# SKYSTAR.net
KiCad netlist of a schematic drawn in EasyEDA Pro
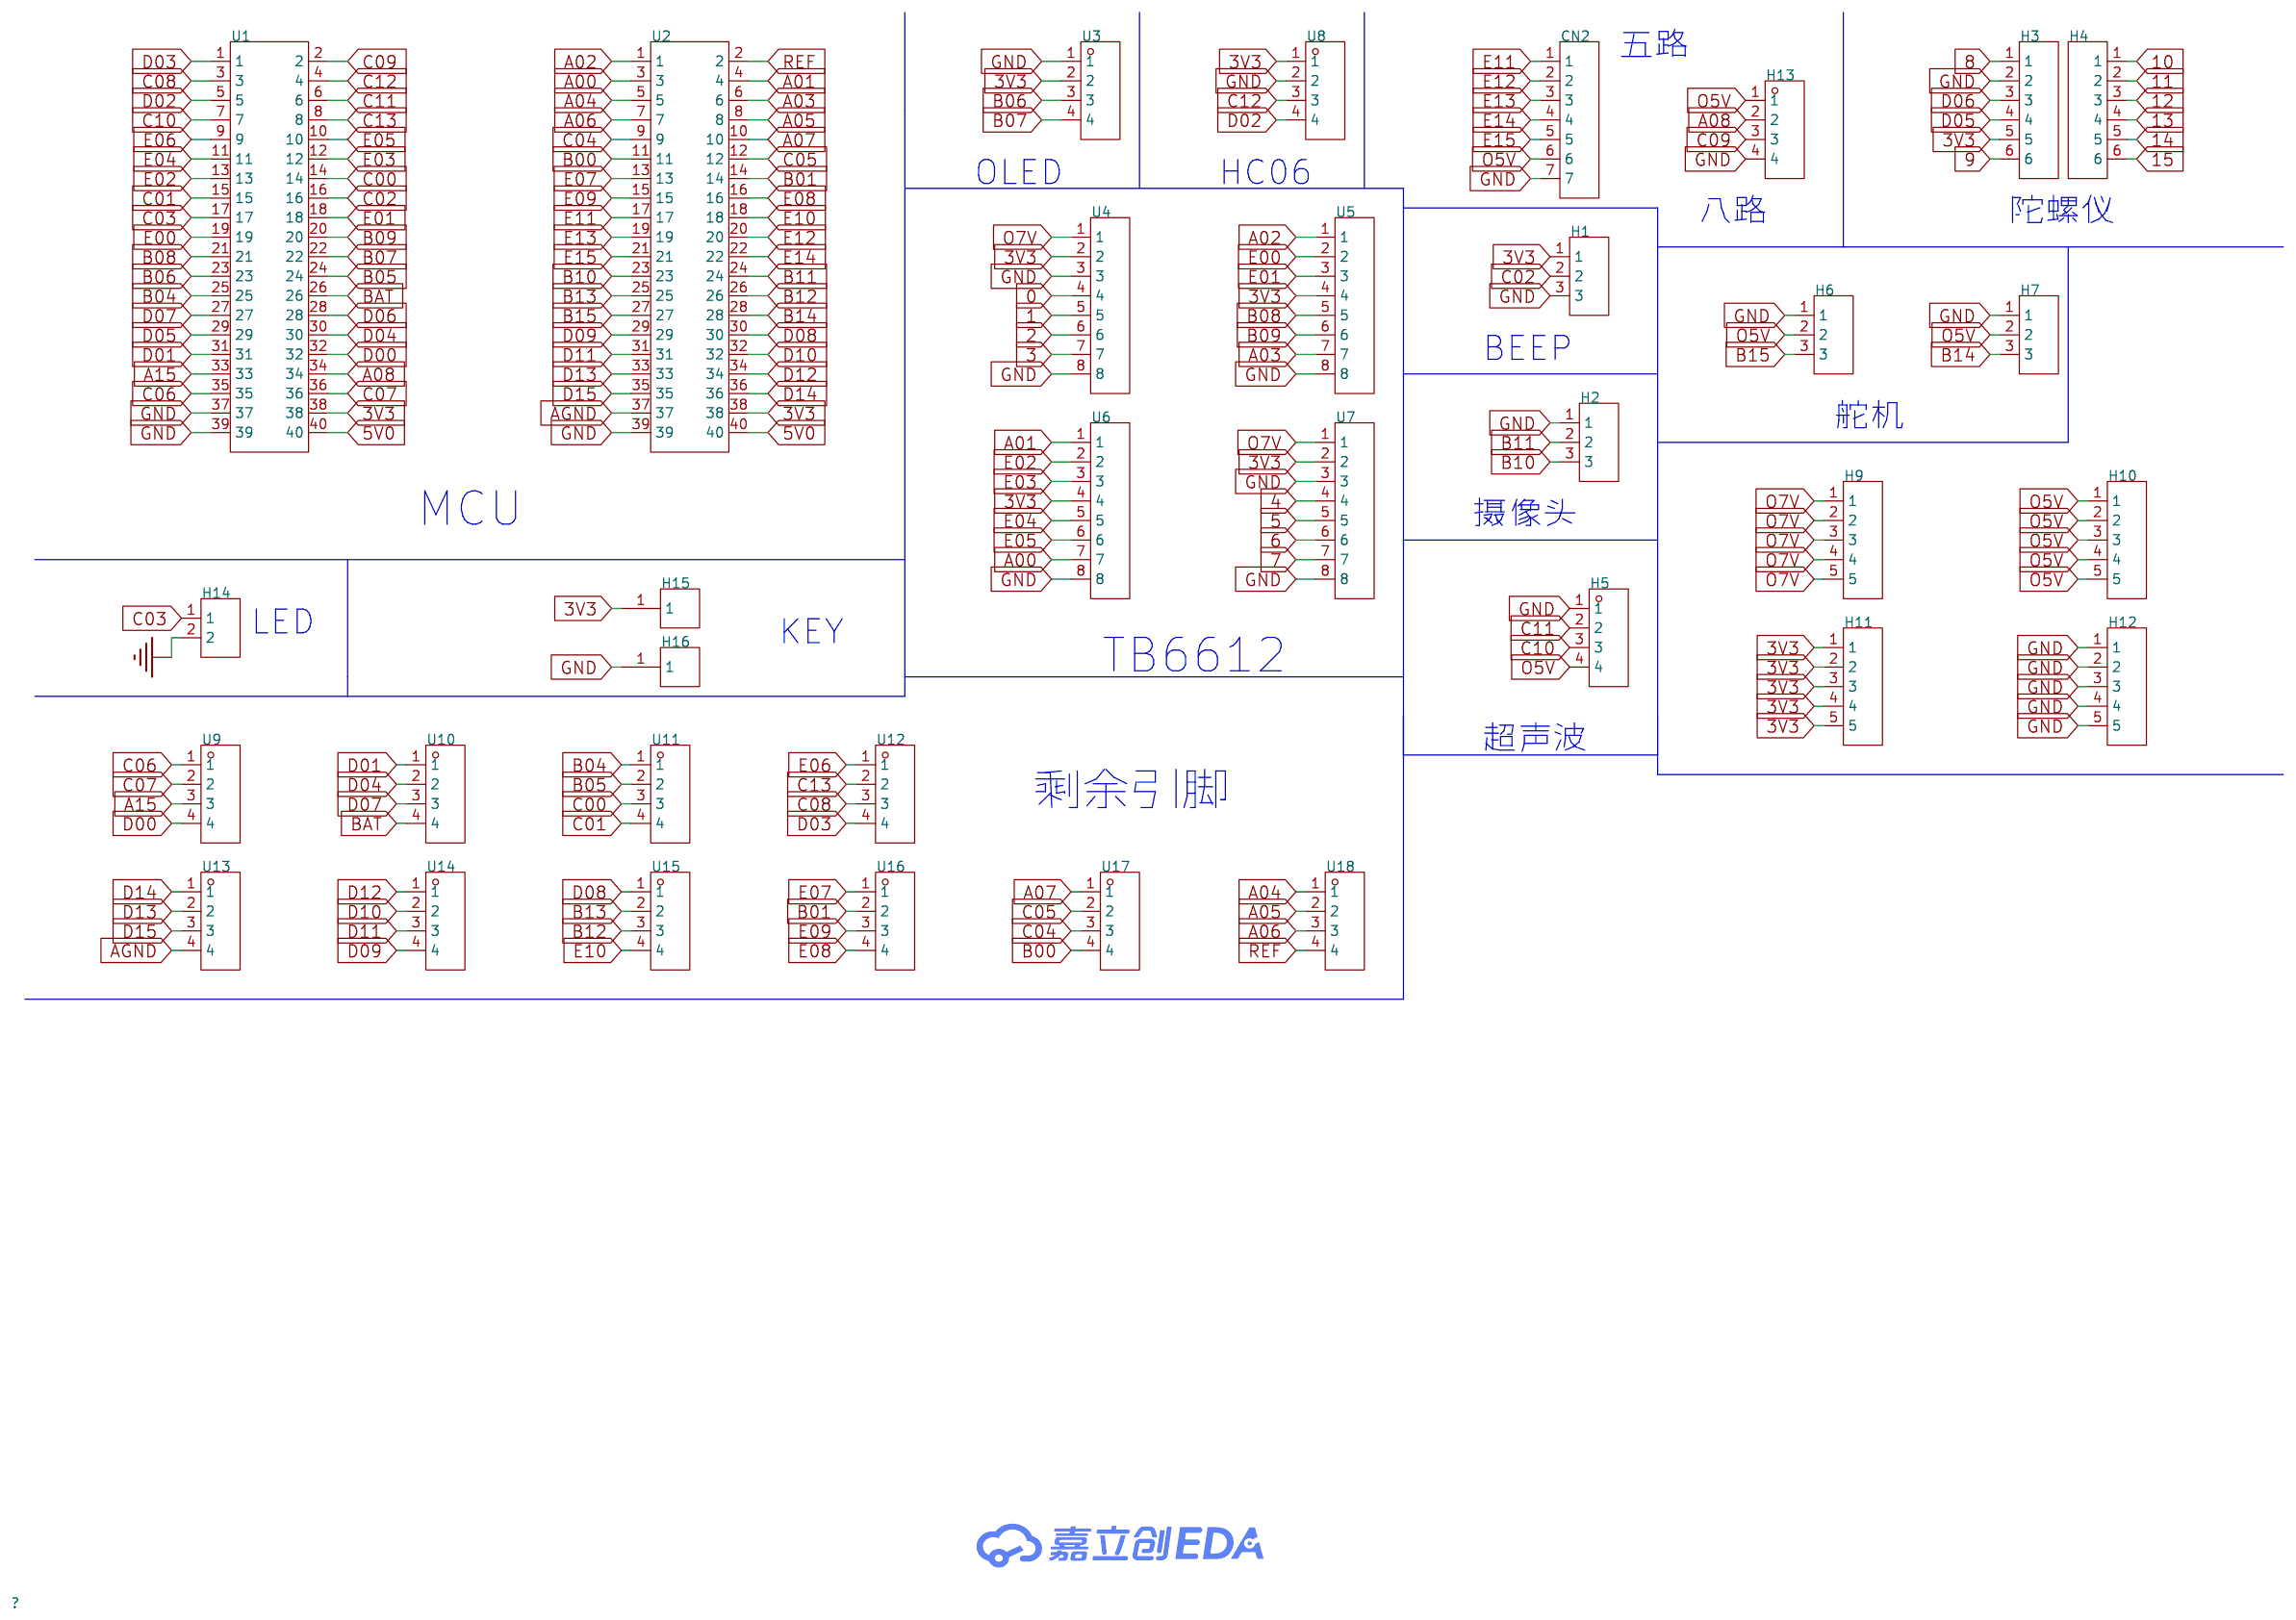
[diagram p0: schematic sheet]

(export (version "E")
  (design (tool "Eeschema 10.0.6"))
  (components
    (comp (ref "CN2")
      (value "DB2ERC-2.54-7P-GN")
      (footprint "easyedapro:CONN-TH_7P-P2.54_DIBO_DB2ERC-2.54-7P-GN")
      (description "连接器类型:板端/插座-闭口;结构:1x7P;间距:2.54mm;颜色:绿色;安装方式:弯针;排数:1;每排PIN数:7;额定电流:5A;额定电压:150V;工作温度:-40°C~+105°C;")
      (fields (field (name "Manufacturer") "DORABO(地博电气)"))
      (libsource (lib "easyedapro") (part "DB2ERC-2.54-7P-GN"))
    )
    (comp (ref "H1")
      (value "PZ254V-11-03P")
      (footprint "easyedapro:HDR-TH_3P-P2.54-V-M")
      (fields (field (name "Manufacturer") "XFCN(兴飞)"))
      (libsource (lib "easyedapro") (part "PZ254V-11-03P_C2937625"))
    )
    (comp (ref "H2")
      (value "PZ254V-11-03P")
      (footprint "easyedapro:HDR-TH_3P-P2.54-V-M")
      (fields (field (name "Manufacturer") "XFCN(兴飞)"))
      (libsource (lib "easyedapro") (part "PZ254V-11-03P_C2937625"))
    )
    (comp (ref "H3")
      (value "PZ254V-11-06P")
      (footprint "easyedapro:HDR-TH_6P-P2.54-V-M")
      (fields (field (name "Manufacturer") "XFCN(兴飞)"))
      (libsource (lib "easyedapro") (part "PZ254V-11-06P"))
    )
    (comp (ref "H4")
      (value "PZ254V-11-06P")
      (footprint "easyedapro:HDR-TH_6P-P2.54-V-M")
      (fields (field (name "Manufacturer") "XFCN(兴飞)"))
      (libsource (lib "easyedapro") (part "PZ254V-11-06P"))
    )
    (comp (ref "H5")
      (value "PZ254V-11-04P")
      (footprint "easyedapro:HDR-TH_4P-P2.54-V-M")
      (fields (field (name "Manufacturer") "XFCN(兴飞)"))
      (libsource (lib "easyedapro") (part "PZ254V-11-04P_C2691448"))
    )
    (comp (ref "H6")
      (value "PZ254V-11-03P")
      (footprint "easyedapro:HDR-TH_3P-P2.54-V-M")
      (fields (field (name "Manufacturer") "XFCN(兴飞)"))
      (libsource (lib "easyedapro") (part "PZ254V-11-03P_C2937625"))
    )
    (comp (ref "H7")
      (value "PZ254V-11-03P")
      (footprint "easyedapro:HDR-TH_3P-P2.54-V-M")
      (fields (field (name "Manufacturer") "XFCN(兴飞)"))
      (libsource (lib "easyedapro") (part "PZ254V-11-03P_C2937625"))
    )
    (comp (ref "H9")
      (value "PZ254V-11-05P")
      (footprint "easyedapro:HDR-TH_5P-P2.54-V-M")
      (fields (field (name "Manufacturer") "XFCN(兴飞)"))
      (libsource (lib "easyedapro") (part "PZ254V-11-05P"))
    )
    (comp (ref "H10")
      (value "PZ254V-11-05P")
      (footprint "easyedapro:HDR-TH_5P-P2.54-V-M")
      (fields (field (name "Manufacturer") "XFCN(兴飞)"))
      (libsource (lib "easyedapro") (part "PZ254V-11-05P"))
    )
    (comp (ref "H11")
      (value "PZ254V-11-05P")
      (footprint "easyedapro:HDR-TH_5P-P2.54-V-M")
      (fields (field (name "Manufacturer") "XFCN(兴飞)"))
      (libsource (lib "easyedapro") (part "PZ254V-11-05P"))
    )
    (comp (ref "H12")
      (value "PZ254V-11-05P")
      (footprint "easyedapro:HDR-TH_5P-P2.54-V-M")
      (fields (field (name "Manufacturer") "XFCN(兴飞)"))
      (libsource (lib "easyedapro") (part "PZ254V-11-05P"))
    )
    (comp (ref "H13")
      (value "PZ254V-11-04P")
      (footprint "easyedapro:HDR-TH_4P-P2.54-V-M")
      (fields (field (name "Manufacturer") "XFCN(兴飞)"))
      (libsource (lib "easyedapro") (part "PZ254V-11-04P_C2691448"))
    )
    (comp (ref "H14")
      (value "PZ254V-11-02P")
      (footprint "easyedapro:HDR-TH_2P-P2.54-V-M")
      (fields (field (name "Manufacturer") "XFCN(兴飞)"))
      (libsource (lib "easyedapro") (part "PZ254V-11-02P"))
    )
    (comp (ref "H15")
      (value "PZ254V-11-01P")
      (footprint "easyedapro:HDR-TH_1P-P2.54-V-M")
      (fields (field (name "Manufacturer") "XFCN(兴飞)"))
      (libsource (lib "easyedapro") (part "PZ254V-11-01P"))
    )
    (comp (ref "H16")
      (value "PZ254V-11-01P")
      (footprint "easyedapro:HDR-TH_1P-P2.54-V-M")
      (fields (field (name "Manufacturer") "XFCN(兴飞)"))
      (libsource (lib "easyedapro") (part "PZ254V-11-01P"))
    )
    (comp (ref "U1")
      (value "PZ2.54-2*20")
      (footprint "easyedapro:HDR-TH_40P-P2.54-V-M-R2-C20-S2.54")
      (description "插针结构:2x20P;间距:2.54mm;安装方式:直插;排数:双排;总PIN位数:40P;触头镀层:金;")
      (fields (field (name "Manufacturer") "ZHOURI(洲日)"))
      (libsource (lib "easyedapro") (part "PZ2.54-2*20"))
    )
    (comp (ref "U2")
      (value "PZ2.54-2*20")
      (footprint "easyedapro:HDR-TH_40P-P2.54-V-M-R2-C20-S2.54")
      (description "插针结构:2x20P;间距:2.54mm;安装方式:直插;排数:双排;总PIN位数:40P;触头镀层:金;")
      (fields (field (name "Manufacturer") "ZHOURI(洲日)"))
      (libsource (lib "easyedapro") (part "PZ2.54-2*20"))
    )
    (comp (ref "U3")
      (value "SIP4-CON4排针")
      (footprint "easyedapro:HDR-TH_4P-P2.54-V-M-3")
      (libsource (lib "easyedapro") (part "SIP4-CON4排针"))
    )
    (comp (ref "U4")
      (value "2.54-1*8")
      (footprint "easyedapro:HDR-TH_8P-P2.54-V-M")
      (description "插针结构:1x8P;间距:2.54mm;排数:单排;总PIN位数:8P;")
      (fields (field (name "Manufacturer") "ZHOURI(洲日)"))
      (libsource (lib "easyedapro") (part "2.54-1*8"))
    )
    (comp (ref "U5")
      (value "2.54-1*8")
      (footprint "easyedapro:HDR-TH_8P-P2.54-V-M")
      (description "插针结构:1x8P;间距:2.54mm;排数:单排;总PIN位数:8P;")
      (fields (field (name "Manufacturer") "ZHOURI(洲日)"))
      (libsource (lib "easyedapro") (part "2.54-1*8"))
    )
    (comp (ref "U6")
      (value "2.54-1*8")
      (footprint "easyedapro:HDR-TH_8P-P2.54-V-M")
      (description "插针结构:1x8P;间距:2.54mm;排数:单排;总PIN位数:8P;")
      (fields (field (name "Manufacturer") "ZHOURI(洲日)"))
      (libsource (lib "easyedapro") (part "2.54-1*8"))
    )
    (comp (ref "U7")
      (value "2.54-1*8")
      (footprint "easyedapro:HDR-TH_8P-P2.54-V-M")
      (description "插针结构:1x8P;间距:2.54mm;排数:单排;总PIN位数:8P;")
      (fields (field (name "Manufacturer") "ZHOURI(洲日)"))
      (libsource (lib "easyedapro") (part "2.54-1*8"))
    )
    (comp (ref "U8")
      (value "SIP4-CON4排针")
      (footprint "easyedapro:HDR-TH_4P-P2.54-V-M-3")
      (libsource (lib "easyedapro") (part "SIP4-CON4排针"))
    )
    (comp (ref "U9")
      (value "SIP4-CON4排针")
      (footprint "easyedapro:HDR-TH_4P-P2.54-V-M-3")
      (libsource (lib "easyedapro") (part "SIP4-CON4排针"))
    )
    (comp (ref "U10")
      (value "SIP4-CON4排针")
      (footprint "easyedapro:HDR-TH_4P-P2.54-V-M-3")
      (libsource (lib "easyedapro") (part "SIP4-CON4排针"))
    )
    (comp (ref "U11")
      (value "SIP4-CON4排针")
      (footprint "easyedapro:HDR-TH_4P-P2.54-V-M-3")
      (libsource (lib "easyedapro") (part "SIP4-CON4排针"))
    )
    (comp (ref "U12")
      (value "SIP4-CON4排针")
      (footprint "easyedapro:HDR-TH_4P-P2.54-V-M-3")
      (libsource (lib "easyedapro") (part "SIP4-CON4排针"))
    )
    (comp (ref "U13")
      (value "SIP4-CON4排针")
      (footprint "easyedapro:HDR-TH_4P-P2.54-V-M-3")
      (libsource (lib "easyedapro") (part "SIP4-CON4排针"))
    )
    (comp (ref "U14")
      (value "SIP4-CON4排针")
      (footprint "easyedapro:HDR-TH_4P-P2.54-V-M-3")
      (libsource (lib "easyedapro") (part "SIP4-CON4排针"))
    )
    (comp (ref "U15")
      (value "SIP4-CON4排针")
      (footprint "easyedapro:HDR-TH_4P-P2.54-V-M-3")
      (libsource (lib "easyedapro") (part "SIP4-CON4排针"))
    )
    (comp (ref "U16")
      (value "SIP4-CON4排针")
      (footprint "easyedapro:HDR-TH_4P-P2.54-V-M-3")
      (libsource (lib "easyedapro") (part "SIP4-CON4排针"))
    )
    (comp (ref "U17")
      (value "SIP4-CON4排针")
      (footprint "easyedapro:HDR-TH_4P-P2.54-V-M-3")
      (libsource (lib "easyedapro") (part "SIP4-CON4排针"))
    )
    (comp (ref "U18")
      (value "SIP4-CON4排针")
      (footprint "easyedapro:HDR-TH_4P-P2.54-V-M-3")
      (libsource (lib "easyedapro") (part "SIP4-CON4排针"))
    )
  )
  (nets
    (net (code "1") (name "0") (class "Default")
      (node (ref "U4") (pin "4") (pinfunction "4_4") (pintype "unspecified"))
    )
    (net (code "2") (name "1") (class "Default")
      (node (ref "U4") (pin "5") (pinfunction "5_5") (pintype "unspecified"))
    )
    (net (code "3") (name "2") (class "Default")
      (node (ref "U4") (pin "6") (pinfunction "6_6") (pintype "unspecified"))
    )
    (net (code "4") (name "3") (class "Default")
      (node (ref "U4") (pin "7") (pinfunction "7_7") (pintype "unspecified"))
    )
    (net (code "5") (name "3V3") (class "Default")
      (node (ref "H1") (pin "1") (pinfunction "1_1") (pintype "unspecified"))
      (node (ref "H11") (pin "1") (pinfunction "1_1") (pintype "unspecified"))
      (node (ref "H11") (pin "2") (pinfunction "2_2") (pintype "unspecified"))
      (node (ref "H11") (pin "3") (pinfunction "3_3") (pintype "unspecified"))
      (node (ref "H11") (pin "4") (pinfunction "4_4") (pintype "unspecified"))
      (node (ref "H11") (pin "5") (pinfunction "5_5") (pintype "unspecified"))
      (node (ref "H15") (pin "1") (pinfunction "1_1") (pintype "unspecified"))
      (node (ref "H3") (pin "5") (pinfunction "5_5") (pintype "unspecified"))
      (node (ref "U1") (pin "38") (pinfunction "38_38") (pintype "unspecified"))
      (node (ref "U2") (pin "38") (pinfunction "38_38") (pintype "unspecified"))
      (node (ref "U3") (pin "2") (pinfunction "2_2") (pintype "unspecified"))
      (node (ref "U4") (pin "2") (pinfunction "2_2") (pintype "unspecified"))
      (node (ref "U5") (pin "4") (pinfunction "4_4") (pintype "unspecified"))
      (node (ref "U6") (pin "4") (pinfunction "4_4") (pintype "unspecified"))
      (node (ref "U7") (pin "2") (pinfunction "2_2") (pintype "unspecified"))
      (node (ref "U8") (pin "1") (pinfunction "1_1") (pintype "unspecified"))
    )
    (net (code "6") (name "4") (class "Default")
      (node (ref "U7") (pin "4") (pinfunction "4_4") (pintype "unspecified"))
    )
    (net (code "7") (name "5") (class "Default")
      (node (ref "U7") (pin "5") (pinfunction "5_5") (pintype "unspecified"))
    )
    (net (code "8") (name "5V0") (class "Default")
      (node (ref "U1") (pin "40") (pinfunction "40_40") (pintype "unspecified"))
      (node (ref "U2") (pin "40") (pinfunction "40_40") (pintype "unspecified"))
    )
    (net (code "9") (name "6") (class "Default")
      (node (ref "U7") (pin "6") (pinfunction "6_6") (pintype "unspecified"))
    )
    (net (code "10") (name "7") (class "Default")
      (node (ref "U7") (pin "7") (pinfunction "7_7") (pintype "unspecified"))
    )
    (net (code "11") (name "8") (class "Default")
      (node (ref "H3") (pin "1") (pinfunction "1_1") (pintype "unspecified"))
    )
    (net (code "12") (name "9") (class "Default")
      (node (ref "H3") (pin "6") (pinfunction "6_6") (pintype "unspecified"))
    )
    (net (code "13") (name "10") (class "Default")
      (node (ref "H4") (pin "1") (pinfunction "1_1") (pintype "unspecified"))
    )
    (net (code "14") (name "11") (class "Default")
      (node (ref "H4") (pin "2") (pinfunction "2_2") (pintype "unspecified"))
    )
    (net (code "15") (name "12") (class "Default")
      (node (ref "H4") (pin "3") (pinfunction "3_3") (pintype "unspecified"))
    )
    (net (code "16") (name "13") (class "Default")
      (node (ref "H4") (pin "4") (pinfunction "4_4") (pintype "unspecified"))
    )
    (net (code "17") (name "14") (class "Default")
      (node (ref "H4") (pin "5") (pinfunction "5_5") (pintype "unspecified"))
    )
    (net (code "18") (name "15") (class "Default")
      (node (ref "H4") (pin "6") (pinfunction "6_6") (pintype "unspecified"))
    )
    (net (code "19") (name "A00") (class "Default")
      (node (ref "U2") (pin "3") (pinfunction "3_3") (pintype "unspecified"))
      (node (ref "U6") (pin "7") (pinfunction "7_7") (pintype "unspecified"))
    )
    (net (code "20") (name "A01") (class "Default")
      (node (ref "U2") (pin "4") (pinfunction "4_4") (pintype "unspecified"))
      (node (ref "U6") (pin "1") (pinfunction "1_1") (pintype "unspecified"))
    )
    (net (code "21") (name "A02") (class "Default")
      (node (ref "U2") (pin "1") (pinfunction "1_1") (pintype "unspecified"))
      (node (ref "U5") (pin "1") (pinfunction "1_1") (pintype "unspecified"))
    )
    (net (code "22") (name "A03") (class "Default")
      (node (ref "U2") (pin "6") (pinfunction "6_6") (pintype "unspecified"))
      (node (ref "U5") (pin "7") (pinfunction "7_7") (pintype "unspecified"))
    )
    (net (code "23") (name "A04") (class "Default")
      (node (ref "U18") (pin "1") (pinfunction "1_1") (pintype "unspecified"))
      (node (ref "U2") (pin "5") (pinfunction "5_5") (pintype "unspecified"))
    )
    (net (code "24") (name "A05") (class "Default")
      (node (ref "U18") (pin "2") (pinfunction "2_2") (pintype "unspecified"))
      (node (ref "U2") (pin "8") (pinfunction "8_8") (pintype "unspecified"))
    )
    (net (code "25") (name "A06") (class "Default")
      (node (ref "U18") (pin "3") (pinfunction "3_3") (pintype "unspecified"))
      (node (ref "U2") (pin "7") (pinfunction "7_7") (pintype "unspecified"))
    )
    (net (code "26") (name "A07") (class "Default")
      (node (ref "U17") (pin "1") (pinfunction "1_1") (pintype "unspecified"))
      (node (ref "U2") (pin "10") (pinfunction "10_10") (pintype "unspecified"))
    )
    (net (code "27") (name "A08") (class "Default")
      (node (ref "H13") (pin "2") (pinfunction "2_2") (pintype "unspecified"))
      (node (ref "U1") (pin "34") (pinfunction "34_34") (pintype "unspecified"))
    )
    (net (code "28") (name "A15") (class "Default")
      (node (ref "U1") (pin "33") (pinfunction "33_33") (pintype "unspecified"))
      (node (ref "U9") (pin "3") (pinfunction "3_3") (pintype "unspecified"))
    )
    (net (code "29") (name "AGND") (class "Default")
      (node (ref "U13") (pin "4") (pinfunction "4_4") (pintype "unspecified"))
      (node (ref "U2") (pin "37") (pinfunction "37_37") (pintype "unspecified"))
    )
    (net (code "30") (name "B00") (class "Default")
      (node (ref "U17") (pin "4") (pinfunction "4_4") (pintype "unspecified"))
      (node (ref "U2") (pin "11") (pinfunction "11_11") (pintype "unspecified"))
    )
    (net (code "31") (name "B01") (class "Default")
      (node (ref "U16") (pin "2") (pinfunction "2_2") (pintype "unspecified"))
      (node (ref "U2") (pin "14") (pinfunction "14_14") (pintype "unspecified"))
    )
    (net (code "32") (name "B04") (class "Default")
      (node (ref "U1") (pin "25") (pinfunction "25_25") (pintype "unspecified"))
      (node (ref "U11") (pin "1") (pinfunction "1_1") (pintype "unspecified"))
    )
    (net (code "33") (name "B05") (class "Default")
      (node (ref "U1") (pin "24") (pinfunction "24_24") (pintype "unspecified"))
      (node (ref "U11") (pin "2") (pinfunction "2_2") (pintype "unspecified"))
    )
    (net (code "34") (name "B06") (class "Default")
      (node (ref "U1") (pin "23") (pinfunction "23_23") (pintype "unspecified"))
      (node (ref "U3") (pin "3") (pinfunction "3_3") (pintype "unspecified"))
    )
    (net (code "35") (name "B07") (class "Default")
      (node (ref "U1") (pin "22") (pinfunction "22_22") (pintype "unspecified"))
      (node (ref "U3") (pin "4") (pinfunction "4_4") (pintype "unspecified"))
    )
    (net (code "36") (name "B08") (class "Default")
      (node (ref "U1") (pin "21") (pinfunction "21_21") (pintype "unspecified"))
      (node (ref "U5") (pin "5") (pinfunction "5_5") (pintype "unspecified"))
    )
    (net (code "37") (name "B09") (class "Default")
      (node (ref "U1") (pin "20") (pinfunction "20_20") (pintype "unspecified"))
      (node (ref "U5") (pin "6") (pinfunction "6_6") (pintype "unspecified"))
    )
    (net (code "38") (name "B10") (class "Default")
      (node (ref "H2") (pin "3") (pinfunction "3_3") (pintype "unspecified"))
      (node (ref "U2") (pin "23") (pinfunction "23_23") (pintype "unspecified"))
    )
    (net (code "39") (name "B11") (class "Default")
      (node (ref "H2") (pin "2") (pinfunction "2_2") (pintype "unspecified"))
      (node (ref "U2") (pin "24") (pinfunction "24_24") (pintype "unspecified"))
    )
    (net (code "40") (name "B12") (class "Default")
      (node (ref "U15") (pin "3") (pinfunction "3_3") (pintype "unspecified"))
      (node (ref "U2") (pin "26") (pinfunction "26_26") (pintype "unspecified"))
    )
    (net (code "41") (name "B13") (class "Default")
      (node (ref "U15") (pin "2") (pinfunction "2_2") (pintype "unspecified"))
      (node (ref "U2") (pin "25") (pinfunction "25_25") (pintype "unspecified"))
    )
    (net (code "42") (name "B14") (class "Default")
      (node (ref "H7") (pin "3") (pinfunction "3_3") (pintype "unspecified"))
      (node (ref "U2") (pin "28") (pinfunction "28_28") (pintype "unspecified"))
    )
    (net (code "43") (name "B15") (class "Default")
      (node (ref "H6") (pin "3") (pinfunction "3_3") (pintype "unspecified"))
      (node (ref "U2") (pin "27") (pinfunction "27_27") (pintype "unspecified"))
    )
    (net (code "44") (name "BAT") (class "Default")
      (node (ref "U1") (pin "26") (pinfunction "26_26") (pintype "unspecified"))
      (node (ref "U10") (pin "4") (pinfunction "4_4") (pintype "unspecified"))
    )
    (net (code "45") (name "C00") (class "Default")
      (node (ref "U1") (pin "14") (pinfunction "14_14") (pintype "unspecified"))
      (node (ref "U11") (pin "3") (pinfunction "3_3") (pintype "unspecified"))
    )
    (net (code "46") (name "C01") (class "Default")
      (node (ref "U1") (pin "15") (pinfunction "15_15") (pintype "unspecified"))
      (node (ref "U11") (pin "4") (pinfunction "4_4") (pintype "unspecified"))
    )
    (net (code "47") (name "C02") (class "Default")
      (node (ref "H1") (pin "2") (pinfunction "2_2") (pintype "unspecified"))
      (node (ref "U1") (pin "16") (pinfunction "16_16") (pintype "unspecified"))
    )
    (net (code "48") (name "C03") (class "Default")
      (node (ref "H14") (pin "1") (pinfunction "1_1") (pintype "unspecified"))
      (node (ref "U1") (pin "17") (pinfunction "17_17") (pintype "unspecified"))
    )
    (net (code "49") (name "C04") (class "Default")
      (node (ref "U17") (pin "3") (pinfunction "3_3") (pintype "unspecified"))
      (node (ref "U2") (pin "9") (pinfunction "9_9") (pintype "unspecified"))
    )
    (net (code "50") (name "C05") (class "Default")
      (node (ref "U17") (pin "2") (pinfunction "2_2") (pintype "unspecified"))
      (node (ref "U2") (pin "12") (pinfunction "12_12") (pintype "unspecified"))
    )
    (net (code "51") (name "C06") (class "Default")
      (node (ref "U1") (pin "35") (pinfunction "35_35") (pintype "unspecified"))
      (node (ref "U9") (pin "1") (pinfunction "1_1") (pintype "unspecified"))
    )
    (net (code "52") (name "C07") (class "Default")
      (node (ref "U1") (pin "36") (pinfunction "36_36") (pintype "unspecified"))
      (node (ref "U9") (pin "2") (pinfunction "2_2") (pintype "unspecified"))
    )
    (net (code "53") (name "C08") (class "Default")
      (node (ref "U1") (pin "3") (pinfunction "3_3") (pintype "unspecified"))
      (node (ref "U12") (pin "3") (pinfunction "3_3") (pintype "unspecified"))
    )
    (net (code "54") (name "C09") (class "Default")
      (node (ref "H13") (pin "3") (pinfunction "3_3") (pintype "unspecified"))
      (node (ref "U1") (pin "2") (pinfunction "2_2") (pintype "unspecified"))
    )
    (net (code "55") (name "C10") (class "Default")
      (node (ref "H5") (pin "3") (pinfunction "3_3") (pintype "unspecified"))
      (node (ref "U1") (pin "7") (pinfunction "7_7") (pintype "unspecified"))
    )
    (net (code "56") (name "C11") (class "Default")
      (node (ref "H5") (pin "2") (pinfunction "2_2") (pintype "unspecified"))
      (node (ref "U1") (pin "6") (pinfunction "6_6") (pintype "unspecified"))
    )
    (net (code "57") (name "C12") (class "Default")
      (node (ref "U1") (pin "4") (pinfunction "4_4") (pintype "unspecified"))
      (node (ref "U8") (pin "3") (pinfunction "3_3") (pintype "unspecified"))
    )
    (net (code "58") (name "C13") (class "Default")
      (node (ref "U1") (pin "8") (pinfunction "8_8") (pintype "unspecified"))
      (node (ref "U12") (pin "2") (pinfunction "2_2") (pintype "unspecified"))
    )
    (net (code "59") (name "D00") (class "Default")
      (node (ref "U1") (pin "32") (pinfunction "32_32") (pintype "unspecified"))
      (node (ref "U9") (pin "4") (pinfunction "4_4") (pintype "unspecified"))
    )
    (net (code "60") (name "D01") (class "Default")
      (node (ref "U1") (pin "31") (pinfunction "31_31") (pintype "unspecified"))
      (node (ref "U10") (pin "1") (pinfunction "1_1") (pintype "unspecified"))
    )
    (net (code "61") (name "D02") (class "Default")
      (node (ref "U1") (pin "5") (pinfunction "5_5") (pintype "unspecified"))
      (node (ref "U8") (pin "4") (pinfunction "4_4") (pintype "unspecified"))
    )
    (net (code "62") (name "D03") (class "Default")
      (node (ref "U1") (pin "1") (pinfunction "1_1") (pintype "unspecified"))
      (node (ref "U12") (pin "4") (pinfunction "4_4") (pintype "unspecified"))
    )
    (net (code "63") (name "D04") (class "Default")
      (node (ref "U1") (pin "30") (pinfunction "30_30") (pintype "unspecified"))
      (node (ref "U10") (pin "2") (pinfunction "2_2") (pintype "unspecified"))
    )
    (net (code "64") (name "D05") (class "Default")
      (node (ref "H3") (pin "4") (pinfunction "4_4") (pintype "unspecified"))
      (node (ref "U1") (pin "29") (pinfunction "29_29") (pintype "unspecified"))
    )
    (net (code "65") (name "D06") (class "Default")
      (node (ref "H3") (pin "3") (pinfunction "3_3") (pintype "unspecified"))
      (node (ref "U1") (pin "28") (pinfunction "28_28") (pintype "unspecified"))
    )
    (net (code "66") (name "D07") (class "Default")
      (node (ref "U1") (pin "27") (pinfunction "27_27") (pintype "unspecified"))
      (node (ref "U10") (pin "3") (pinfunction "3_3") (pintype "unspecified"))
    )
    (net (code "67") (name "D08") (class "Default")
      (node (ref "U15") (pin "1") (pinfunction "1_1") (pintype "unspecified"))
      (node (ref "U2") (pin "30") (pinfunction "30_30") (pintype "unspecified"))
    )
    (net (code "68") (name "D09") (class "Default")
      (node (ref "U14") (pin "4") (pinfunction "4_4") (pintype "unspecified"))
      (node (ref "U2") (pin "29") (pinfunction "29_29") (pintype "unspecified"))
    )
    (net (code "69") (name "D10") (class "Default")
      (node (ref "U14") (pin "2") (pinfunction "2_2") (pintype "unspecified"))
      (node (ref "U2") (pin "32") (pinfunction "32_32") (pintype "unspecified"))
    )
    (net (code "70") (name "D11") (class "Default")
      (node (ref "U14") (pin "3") (pinfunction "3_3") (pintype "unspecified"))
      (node (ref "U2") (pin "31") (pinfunction "31_31") (pintype "unspecified"))
    )
    (net (code "71") (name "D12") (class "Default")
      (node (ref "U14") (pin "1") (pinfunction "1_1") (pintype "unspecified"))
      (node (ref "U2") (pin "34") (pinfunction "34_34") (pintype "unspecified"))
    )
    (net (code "72") (name "D13") (class "Default")
      (node (ref "U13") (pin "2") (pinfunction "2_2") (pintype "unspecified"))
      (node (ref "U2") (pin "33") (pinfunction "33_33") (pintype "unspecified"))
    )
    (net (code "73") (name "D14") (class "Default")
      (node (ref "U13") (pin "1") (pinfunction "1_1") (pintype "unspecified"))
      (node (ref "U2") (pin "36") (pinfunction "36_36") (pintype "unspecified"))
    )
    (net (code "74") (name "D15") (class "Default")
      (node (ref "U13") (pin "3") (pinfunction "3_3") (pintype "unspecified"))
      (node (ref "U2") (pin "35") (pinfunction "35_35") (pintype "unspecified"))
    )
    (net (code "75") (name "E00") (class "Default")
      (node (ref "U1") (pin "19") (pinfunction "19_19") (pintype "unspecified"))
      (node (ref "U5") (pin "2") (pinfunction "2_2") (pintype "unspecified"))
    )
    (net (code "76") (name "E01") (class "Default")
      (node (ref "U1") (pin "18") (pinfunction "18_18") (pintype "unspecified"))
      (node (ref "U5") (pin "3") (pinfunction "3_3") (pintype "unspecified"))
    )
    (net (code "77") (name "E02") (class "Default")
      (node (ref "U1") (pin "13") (pinfunction "13_13") (pintype "unspecified"))
      (node (ref "U6") (pin "2") (pinfunction "2_2") (pintype "unspecified"))
    )
    (net (code "78") (name "E03") (class "Default")
      (node (ref "U1") (pin "12") (pinfunction "12_12") (pintype "unspecified"))
      (node (ref "U6") (pin "3") (pinfunction "3_3") (pintype "unspecified"))
    )
    (net (code "79") (name "E04") (class "Default")
      (node (ref "U1") (pin "11") (pinfunction "11_11") (pintype "unspecified"))
      (node (ref "U6") (pin "5") (pinfunction "5_5") (pintype "unspecified"))
    )
    (net (code "80") (name "E05") (class "Default")
      (node (ref "U1") (pin "10") (pinfunction "10_10") (pintype "unspecified"))
      (node (ref "U6") (pin "6") (pinfunction "6_6") (pintype "unspecified"))
    )
    (net (code "81") (name "E06") (class "Default")
      (node (ref "U1") (pin "9") (pinfunction "9_9") (pintype "unspecified"))
      (node (ref "U12") (pin "1") (pinfunction "1_1") (pintype "unspecified"))
    )
    (net (code "82") (name "E07") (class "Default")
      (node (ref "U16") (pin "1") (pinfunction "1_1") (pintype "unspecified"))
      (node (ref "U2") (pin "13") (pinfunction "13_13") (pintype "unspecified"))
    )
    (net (code "83") (name "E08") (class "Default")
      (node (ref "U16") (pin "4") (pinfunction "4_4") (pintype "unspecified"))
      (node (ref "U2") (pin "16") (pinfunction "16_16") (pintype "unspecified"))
    )
    (net (code "84") (name "E09") (class "Default")
      (node (ref "U16") (pin "3") (pinfunction "3_3") (pintype "unspecified"))
      (node (ref "U2") (pin "15") (pinfunction "15_15") (pintype "unspecified"))
    )
    (net (code "85") (name "E10") (class "Default")
      (node (ref "U15") (pin "4") (pinfunction "4_4") (pintype "unspecified"))
      (node (ref "U2") (pin "18") (pinfunction "18_18") (pintype "unspecified"))
    )
    (net (code "86") (name "E11") (class "Default")
      (node (ref "CN2") (pin "1") (pinfunction "1_1") (pintype "unspecified"))
      (node (ref "U2") (pin "17") (pinfunction "17_17") (pintype "unspecified"))
    )
    (net (code "87") (name "E12") (class "Default")
      (node (ref "CN2") (pin "2") (pinfunction "2_2") (pintype "unspecified"))
      (node (ref "U2") (pin "20") (pinfunction "20_20") (pintype "unspecified"))
    )
    (net (code "88") (name "E13") (class "Default")
      (node (ref "CN2") (pin "3") (pinfunction "3_3") (pintype "unspecified"))
      (node (ref "U2") (pin "19") (pinfunction "19_19") (pintype "unspecified"))
    )
    (net (code "89") (name "E14") (class "Default")
      (node (ref "CN2") (pin "4") (pinfunction "4_4") (pintype "unspecified"))
      (node (ref "U2") (pin "22") (pinfunction "22_22") (pintype "unspecified"))
    )
    (net (code "90") (name "E15") (class "Default")
      (node (ref "CN2") (pin "5") (pinfunction "5_5") (pintype "unspecified"))
      (node (ref "U2") (pin "21") (pinfunction "21_21") (pintype "unspecified"))
    )
    (net (code "91") (name "GND") (class "Default")
      (node (ref "CN2") (pin "7") (pinfunction "7_7") (pintype "unspecified"))
      (node (ref "H1") (pin "3") (pinfunction "3_3") (pintype "unspecified"))
      (node (ref "H12") (pin "1") (pinfunction "1_1") (pintype "unspecified"))
      (node (ref "H12") (pin "2") (pinfunction "2_2") (pintype "unspecified"))
      (node (ref "H12") (pin "3") (pinfunction "3_3") (pintype "unspecified"))
      (node (ref "H12") (pin "4") (pinfunction "4_4") (pintype "unspecified"))
      (node (ref "H12") (pin "5") (pinfunction "5_5") (pintype "unspecified"))
      (node (ref "H13") (pin "4") (pinfunction "4_4") (pintype "unspecified"))
      (node (ref "H14") (pin "2") (pinfunction "2_2") (pintype "unspecified"))
      (node (ref "H16") (pin "1") (pinfunction "1_1") (pintype "unspecified"))
      (node (ref "H2") (pin "1") (pinfunction "1_1") (pintype "unspecified"))
      (node (ref "H3") (pin "2") (pinfunction "2_2") (pintype "unspecified"))
      (node (ref "H5") (pin "1") (pinfunction "1_1") (pintype "unspecified"))
      (node (ref "H6") (pin "1") (pinfunction "1_1") (pintype "unspecified"))
      (node (ref "H7") (pin "1") (pinfunction "1_1") (pintype "unspecified"))
      (node (ref "U1") (pin "37") (pinfunction "37_37") (pintype "unspecified"))
      (node (ref "U1") (pin "39") (pinfunction "39_39") (pintype "unspecified"))
      (node (ref "U2") (pin "39") (pinfunction "39_39") (pintype "unspecified"))
      (node (ref "U3") (pin "1") (pinfunction "1_1") (pintype "unspecified"))
      (node (ref "U4") (pin "3") (pinfunction "3_3") (pintype "unspecified"))
      (node (ref "U4") (pin "8") (pinfunction "8_8") (pintype "unspecified"))
      (node (ref "U5") (pin "8") (pinfunction "8_8") (pintype "unspecified"))
      (node (ref "U6") (pin "8") (pinfunction "8_8") (pintype "unspecified"))
      (node (ref "U7") (pin "3") (pinfunction "3_3") (pintype "unspecified"))
      (node (ref "U7") (pin "8") (pinfunction "8_8") (pintype "unspecified"))
      (node (ref "U8") (pin "2") (pinfunction "2_2") (pintype "unspecified"))
    )
    (net (code "92") (name "O5V") (class "Default")
      (node (ref "CN2") (pin "6") (pinfunction "6_6") (pintype "unspecified"))
      (node (ref "H10") (pin "1") (pinfunction "1_1") (pintype "unspecified"))
      (node (ref "H10") (pin "2") (pinfunction "2_2") (pintype "unspecified"))
      (node (ref "H10") (pin "3") (pinfunction "3_3") (pintype "unspecified"))
      (node (ref "H10") (pin "4") (pinfunction "4_4") (pintype "unspecified"))
      (node (ref "H10") (pin "5") (pinfunction "5_5") (pintype "unspecified"))
      (node (ref "H13") (pin "1") (pinfunction "1_1") (pintype "unspecified"))
      (node (ref "H5") (pin "4") (pinfunction "4_4") (pintype "unspecified"))
      (node (ref "H6") (pin "2") (pinfunction "2_2") (pintype "unspecified"))
      (node (ref "H7") (pin "2") (pinfunction "2_2") (pintype "unspecified"))
    )
    (net (code "93") (name "O7V") (class "Default")
      (node (ref "H9") (pin "1") (pinfunction "1_1") (pintype "unspecified"))
      (node (ref "H9") (pin "2") (pinfunction "2_2") (pintype "unspecified"))
      (node (ref "H9") (pin "3") (pinfunction "3_3") (pintype "unspecified"))
      (node (ref "H9") (pin "4") (pinfunction "4_4") (pintype "unspecified"))
      (node (ref "H9") (pin "5") (pinfunction "5_5") (pintype "unspecified"))
      (node (ref "U4") (pin "1") (pinfunction "1_1") (pintype "unspecified"))
      (node (ref "U7") (pin "1") (pinfunction "1_1") (pintype "unspecified"))
    )
    (net (code "94") (name "REF") (class "Default")
      (node (ref "U18") (pin "4") (pinfunction "4_4") (pintype "unspecified"))
      (node (ref "U2") (pin "2") (pinfunction "2_2") (pintype "unspecified"))
    )
  )
)
